# UNG_8088_EVB_LAN9252-SPI_LAN9252-1.net
KiCad netlist of a schematic drawn in Altium Designer
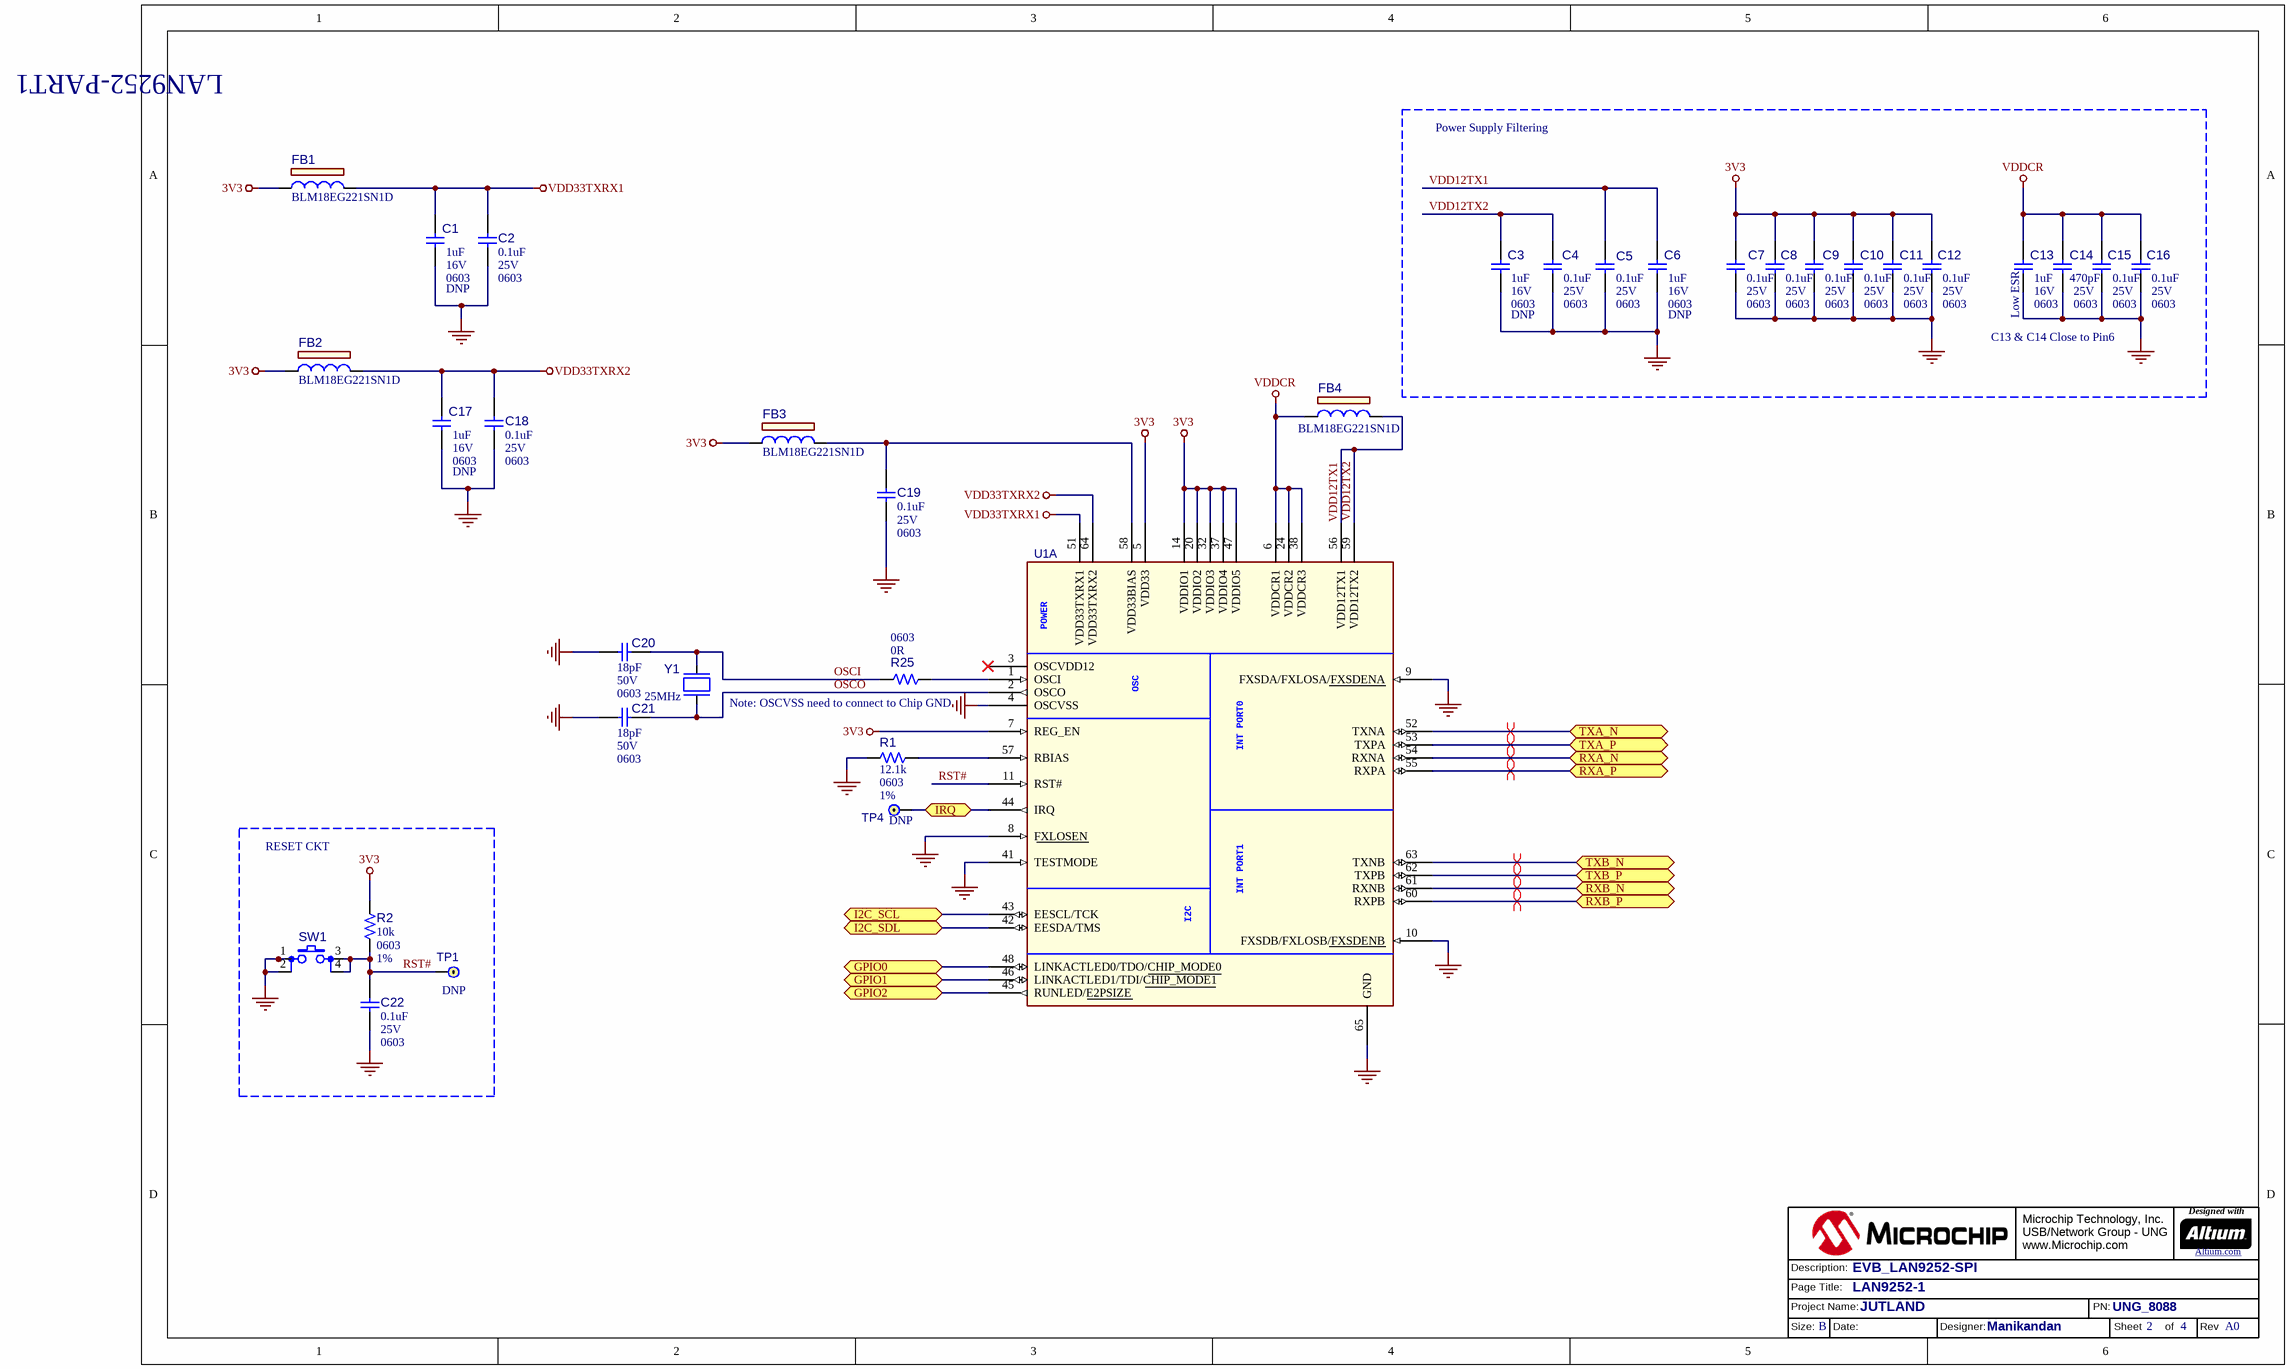
[diagram p0: UNG_8088_EVB_LAN9252-SPI_LAN9252-1.SchDoc]

(export (version "E")
  (design (tool "Eeschema 10.0.6"))
  (components
    (comp (ref "C1")
      (value "1uF")
      (footprint "CAP_C_0603")
      (description "Capacitor")
      (fields
        (field (name "VOLTAGE") "16V")
        (field (name "PACKAGE") "0603")
        (field (name "TOLERANCE") "10%")
        (field (name "POPULATED") "DNP")
        (field (name "Comment") "Capacitor NP")
      )
      (libsource (lib "MCHP-CDB-Offline") (part "Capacitor NP"))
    )
    (comp (ref "C2")
      (value "0.1uF")
      (footprint "CAP_C_0603")
      (description "Capacitor")
      (fields
        (field (name "VOLTAGE") "25V")
        (field (name "PACKAGE") "0603")
        (field (name "TOLERANCE") "20%")
        (field (name "Comment") "Capacitor NP")
      )
      (libsource (lib "MCHP-CDB-Offline") (part "Capacitor NP"))
    )
    (comp (ref "C3")
      (value "1uF")
      (footprint "CAP_C_0603")
      (description "Capacitor")
      (fields
        (field (name "VOLTAGE") "16V")
        (field (name "PACKAGE") "0603")
        (field (name "TOLERANCE") "10%")
        (field (name "POPULATED") "DNP")
        (field (name "Comment") "Capacitor NP")
      )
      (libsource (lib "MCHP-CDB-Offline") (part "Capacitor NP"))
    )
    (comp (ref "C4")
      (value "0.1uF")
      (footprint "CAP_C_0603")
      (description "Capacitor")
      (fields
        (field (name "VOLTAGE") "25V")
        (field (name "PACKAGE") "0603")
        (field (name "TOLERANCE") "20%")
        (field (name "Comment") "Capacitor NP")
      )
      (libsource (lib "MCHP-CDB-Offline") (part "Capacitor NP"))
    )
    (comp (ref "C5")
      (value "0.1uF")
      (footprint "CAP_C_0603")
      (description "Capacitor")
      (fields
        (field (name "VOLTAGE") "25V")
        (field (name "PACKAGE") "0603")
        (field (name "TOLERANCE") "20%")
        (field (name "Comment") "Capacitor NP")
      )
      (libsource (lib "MCHP-CDB-Offline") (part "Capacitor NP"))
    )
    (comp (ref "C6")
      (value "1uF")
      (footprint "CAP_C_0603")
      (description "Capacitor")
      (fields
        (field (name "VOLTAGE") "16V")
        (field (name "PACKAGE") "0603")
        (field (name "TOLERANCE") "10%")
        (field (name "POPULATED") "DNP")
        (field (name "Comment") "Capacitor NP")
      )
      (libsource (lib "MCHP-CDB-Offline") (part "Capacitor NP"))
    )
    (comp (ref "C7")
      (value "0.1uF")
      (footprint "CAP_C_0603")
      (description "Capacitor")
      (fields
        (field (name "VOLTAGE") "25V")
        (field (name "PACKAGE") "0603")
        (field (name "TOLERANCE") "20%")
        (field (name "Comment") "Capacitor NP")
      )
      (libsource (lib "MCHP-CDB-Offline") (part "Capacitor NP"))
    )
    (comp (ref "C8")
      (value "0.1uF")
      (footprint "CAP_C_0603")
      (description "Capacitor")
      (fields
        (field (name "VOLTAGE") "25V")
        (field (name "PACKAGE") "0603")
        (field (name "TOLERANCE") "20%")
        (field (name "Comment") "Capacitor NP")
      )
      (libsource (lib "MCHP-CDB-Offline") (part "Capacitor NP"))
    )
    (comp (ref "C9")
      (value "0.1uF")
      (footprint "CAP_C_0603")
      (description "Capacitor")
      (fields
        (field (name "VOLTAGE") "25V")
        (field (name "PACKAGE") "0603")
        (field (name "TOLERANCE") "20%")
        (field (name "Comment") "Capacitor NP")
      )
      (libsource (lib "MCHP-CDB-Offline") (part "Capacitor NP"))
    )
    (comp (ref "C10")
      (value "0.1uF")
      (footprint "CAP_C_0603")
      (description "Capacitor")
      (fields
        (field (name "VOLTAGE") "25V")
        (field (name "PACKAGE") "0603")
        (field (name "TOLERANCE") "20%")
        (field (name "Comment") "Capacitor NP")
      )
      (libsource (lib "MCHP-CDB-Offline") (part "Capacitor NP"))
    )
    (comp (ref "C11")
      (value "0.1uF")
      (footprint "CAP_C_0603")
      (description "Capacitor")
      (fields
        (field (name "VOLTAGE") "25V")
        (field (name "PACKAGE") "0603")
        (field (name "TOLERANCE") "20%")
        (field (name "Comment") "Capacitor NP")
      )
      (libsource (lib "MCHP-CDB-Offline") (part "Capacitor NP"))
    )
    (comp (ref "C12")
      (value "0.1uF")
      (footprint "CAP_C_0603")
      (description "Capacitor")
      (fields
        (field (name "VOLTAGE") "25V")
        (field (name "PACKAGE") "0603")
        (field (name "TOLERANCE") "20%")
        (field (name "Comment") "Capacitor NP")
      )
      (libsource (lib "MCHP-CDB-Offline") (part "Capacitor NP"))
    )
    (comp (ref "C13")
      (value "1uF")
      (footprint "CAP_C_0603")
      (description "Capacitor")
      (fields
        (field (name "VOLTAGE") "16V")
        (field (name "PACKAGE") "0603")
        (field (name "TOLERANCE") "10%")
        (field (name "Comment") "Capacitor NP")
      )
      (libsource (lib "MCHP-CDB-Offline") (part "Capacitor NP"))
    )
    (comp (ref "C14")
      (value "470pF")
      (footprint "CAP_C_0603")
      (description "Capacitor")
      (fields
        (field (name "VOLTAGE") "25V")
        (field (name "PACKAGE") "0603")
        (field (name "TOLERANCE") "5%")
        (field (name "Comment") "Capacitor NP")
      )
      (libsource (lib "MCHP-CDB-Offline") (part "Capacitor NP"))
    )
    (comp (ref "C15")
      (value "0.1uF")
      (footprint "CAP_C_0603")
      (description "Capacitor")
      (fields
        (field (name "VOLTAGE") "25V")
        (field (name "PACKAGE") "0603")
        (field (name "TOLERANCE") "20%")
        (field (name "Comment") "Capacitor NP")
      )
      (libsource (lib "MCHP-CDB-Offline") (part "Capacitor NP"))
    )
    (comp (ref "C16")
      (value "0.1uF")
      (footprint "CAP_C_0603")
      (description "Capacitor")
      (fields
        (field (name "VOLTAGE") "25V")
        (field (name "PACKAGE") "0603")
        (field (name "TOLERANCE") "20%")
        (field (name "Comment") "Capacitor NP")
      )
      (libsource (lib "MCHP-CDB-Offline") (part "Capacitor NP"))
    )
    (comp (ref "C17")
      (value "1uF")
      (footprint "CAP_C_0603")
      (description "Capacitor")
      (fields
        (field (name "VOLTAGE") "16V")
        (field (name "PACKAGE") "0603")
        (field (name "TOLERANCE") "10%")
        (field (name "POPULATED") "DNP")
        (field (name "Comment") "Capacitor NP")
      )
      (libsource (lib "MCHP-CDB-Offline") (part "Capacitor NP"))
    )
    (comp (ref "C18")
      (value "0.1uF")
      (footprint "CAP_C_0603")
      (description "Capacitor")
      (fields
        (field (name "VOLTAGE") "25V")
        (field (name "PACKAGE") "0603")
        (field (name "TOLERANCE") "20%")
        (field (name "Comment") "Capacitor NP")
      )
      (libsource (lib "MCHP-CDB-Offline") (part "Capacitor NP"))
    )
    (comp (ref "C19")
      (value "0.1uF")
      (footprint "CAP_C_0603")
      (description "Capacitor")
      (fields
        (field (name "VOLTAGE") "25V")
        (field (name "PACKAGE") "0603")
        (field (name "TOLERANCE") "20%")
        (field (name "Comment") "Capacitor NP")
      )
      (libsource (lib "MCHP-CDB-Offline") (part "Capacitor NP"))
    )
    (comp (ref "C20")
      (value "18pF")
      (footprint "CAP_C_0603")
      (description "Capacitor")
      (fields
        (field (name "VOLTAGE") "50V")
        (field (name "PACKAGE") "0603")
        (field (name "TOLERANCE") "5%")
        (field (name "Comment") "Capacitor NP")
      )
      (libsource (lib "MCHP-CDB-Offline") (part "Capacitor NP"))
    )
    (comp (ref "C21")
      (value "18pF")
      (footprint "CAP_C_0603")
      (description "Capacitor")
      (fields
        (field (name "VOLTAGE") "50V")
        (field (name "PACKAGE") "0603")
        (field (name "TOLERANCE") "5%")
        (field (name "Comment") "Capacitor NP")
      )
      (libsource (lib "MCHP-CDB-Offline") (part "Capacitor NP"))
    )
    (comp (ref "C22")
      (value "0.1uF")
      (footprint "CAP_C_0603")
      (description "Capacitor")
      (fields
        (field (name "VOLTAGE") "25V")
        (field (name "PACKAGE") "0603")
        (field (name "TOLERANCE") "20%")
        (field (name "Comment") "Capacitor NP")
      )
      (libsource (lib "MCHP-CDB-Offline") (part "Capacitor NP"))
    )
    (comp (ref "FB1")
      (value "BLM18EG221SN1D")
      (footprint "SMD_0603")
      (description "FERRITE BEAD 2A 220OHM 0603")
      (fields (field (name "Comment") "FERRITE BLM18EG221SN1D") (field (name "OWNER") "Manikandan"))
      (libsource (lib "UNG_MISC") (part "FERRITE BLM18EG221SN1D"))
    )
    (comp (ref "FB2")
      (value "BLM18EG221SN1D")
      (footprint "SMD_0603")
      (description "FERRITE BEAD 2A 220OHM 0603")
      (fields (field (name "Comment") "FERRITE BLM18EG221SN1D") (field (name "OWNER") "Manikandan"))
      (libsource (lib "UNG_MISC") (part "FERRITE BLM18EG221SN1D"))
    )
    (comp (ref "FB3")
      (value "BLM18EG221SN1D")
      (footprint "SMD_0603")
      (description "FERRITE BEAD 2A 220OHM 0603")
      (fields (field (name "Comment") "FERRITE BLM18EG221SN1D") (field (name "OWNER") "Manikandan"))
      (libsource (lib "UNG_MISC") (part "FERRITE BLM18EG221SN1D"))
    )
    (comp (ref "FB4")
      (value "BLM18EG221SN1D")
      (footprint "SMD_0603")
      (description "FERRITE BEAD 2A 220OHM 0603")
      (fields (field (name "Comment") "FERRITE BLM18EG221SN1D") (field (name "OWNER") "Manikandan"))
      (libsource (lib "UNG_MISC") (part "FERRITE BLM18EG221SN1D"))
    )
    (comp (ref "R1")
      (value "12.1k")
      (footprint "RES_C_0603")
      (description "Resistor")
      (fields
        (field (name "PACKAGE") "0603")
        (field (name "TOLERANCE") "1%")
        (field (name "VOLTAGE") "75V")
        (field (name "POWER") "1/10W")
      )
      (libsource (lib "MCHP-CDB-Offline") (part "Resistor"))
    )
    (comp (ref "R2")
      (value "10k")
      (footprint "RES_C_0603")
      (description "Resistor")
      (fields
        (field (name "PACKAGE") "0603")
        (field (name "TOLERANCE") "1%")
        (field (name "VOLTAGE") "100V")
        (field (name "POWER") "1/16W")
        (field (name "OWNER") "Jairuz Agang-ang")
      )
      (libsource (lib "MCHP-CDB-Offline") (part "Resistor"))
    )
    (comp (ref "R25")
      (value "0R")
      (footprint "RES_C_0603")
      (description "Resistor")
      (fields (field (name "PACKAGE") "0603") (field (name "POWER") "1/10W"))
      (libsource (lib "MCHP-CDB-Offline") (part "Resistor"))
    )
    (comp (ref "SW1")
      (value "Switch TACT 4 Pin PTS810")
      (footprint "SW_MOM_4M2X3M2")
      (description "SWITCH TACTILE SPST-NO 0.05A 16V PTS810 4.2 x 3.2 mm")
      (fields
        (field (name "MANUFACTURER") "C&K Components")
        (field (name "MANUFACTURER PART NUMBER") "PTS810 SJM 250 SMTR LFS")
      )
      (libsource (lib "UNG_SWITCHES") (part "Switch TACT 4 Pin PTS810"))
    )
    (comp (ref "TP1")
      (value "Jumper")
      (footprint "TP_PAD51D36")
      (description "Test Pad TH 51X36")
      (fields (field (name "MANUFACTURER PART NUMBER") "none") (field (name "POPULATED") "DNP"))
      (libsource (lib "UNG_CONNECTORS") (part "TEST PAD TH 51X36"))
    )
    (comp (ref "TP4")
      (value "Jumper")
      (footprint "TP_PAD51D36")
      (description "Test Pad TH 51X36")
      (fields (field (name "MANUFACTURER PART NUMBER") "none") (field (name "POPULATED") "DNP"))
      (libsource (lib "UNG_CONNECTORS") (part "TEST PAD TH 51X36"))
    )
    (comp (ref "U1")
      (value "~")
      (footprint "QFN-64_9x9_EP6SQ")
      (description "IC, 2/3-Port EtherCAT® Slave Controller, QFN64")
      (fields (field (name "OWNER") "Manikandan"))
      (libsource (lib "UNG_UNG") (part "LAN9252_QFN64"))
    )
    (comp (ref "Y1")
      (value "XTAL 25MHz HC49/US")
      (footprint "CRYSTAL_HC49-SMD-B")
      (description "Crystal 25MHz HC49/US")
      (fields
        (field (name "MANUFACTURER") "Murata Electronics North America")
        (field (name "FREQUENCY") "25MHz")
      )
      (libsource (lib "UNG_XTAL_OSC") (part "XTAL 25MHz HC49US"))
    )
  )
  (nets
    (net (code "1") (name "/GPIO0") (class "Default")
      (node (ref "U1") (pin "48") (pinfunction "LINKACTLED0/TDO/CHIP_MODE0_48") (pintype "bidirectional"))
    )
    (net (code "2") (name "/GPIO1") (class "Default")
      (node (ref "U1") (pin "46") (pinfunction "LINKACTLED1/TDI/CHIP_MODE1_46") (pintype "bidirectional"))
    )
    (net (code "3") (name "/GPIO2") (class "Default")
      (node (ref "U1") (pin "45") (pinfunction "RUNLED/E2PSIZE_45") (pintype "output"))
    )
    (net (code "4") (name "/I2C_SCL") (class "Default")
      (node (ref "U1") (pin "43") (pinfunction "EESCL/TCK_43") (pintype "bidirectional"))
    )
    (net (code "5") (name "/I2C_SDL") (class "Default")
      (node (ref "U1") (pin "42") (pinfunction "EESDA/TMS_42") (pintype "bidirectional"))
    )
    (net (code "6") (name "/IRQ") (class "Default")
      (node (ref "TP4") (pin "1") (pinfunction "P1_1") (pintype "passive"))
      (node (ref "U1") (pin "44") (pinfunction "IRQ_44") (pintype "output"))
    )
    (net (code "7") (name "/OSCI") (class "Default")
      (node (ref "C20") (pin "2") (pinfunction "2_2") (pintype "passive"))
      (node (ref "R25") (pin "1") (pinfunction "1_1") (pintype "passive"))
      (node (ref "Y1") (pin "2") (pinfunction "Osc2_2") (pintype "passive"))
    )
    (net (code "8") (name "/OSCO") (class "Default")
      (node (ref "C21") (pin "2") (pinfunction "2_2") (pintype "passive"))
      (node (ref "U1") (pin "2") (pinfunction "OSCO_2") (pintype "output"))
      (node (ref "Y1") (pin "1") (pinfunction "Osc1_1") (pintype "passive"))
    )
    (net (code "9") (name "/RST#") (class "Default")
      (node (ref "C22") (pin "2") (pinfunction "2_2") (pintype "passive"))
      (node (ref "R2") (pin "1") (pinfunction "1_1") (pintype "passive"))
      (node (ref "SW1") (pin "3") (pinfunction "3_3") (pintype "passive"))
      (node (ref "SW1") (pin "4") (pinfunction "4_4") (pintype "passive"))
      (node (ref "TP1") (pin "1") (pinfunction "P1_1") (pintype "passive"))
      (node (ref "U1") (pin "11") (pinfunction "RST#_11") (pintype "input"))
    )
    (net (code "10") (name "/RXA_N") (class "Default")
      (node (ref "U1") (pin "54") (pinfunction "RXNA_54") (pintype "bidirectional"))
    )
    (net (code "11") (name "/RXA_P") (class "Default")
      (node (ref "U1") (pin "55") (pinfunction "RXPA_55") (pintype "bidirectional"))
    )
    (net (code "12") (name "/RXB_N") (class "Default")
      (node (ref "U1") (pin "61") (pinfunction "RXNB_61") (pintype "bidirectional"))
    )
    (net (code "13") (name "/RXB_P") (class "Default")
      (node (ref "U1") (pin "60") (pinfunction "RXPB_60") (pintype "bidirectional"))
    )
    (net (code "14") (name "/TXA_N") (class "Default")
      (node (ref "U1") (pin "52") (pinfunction "TXNA_52") (pintype "bidirectional"))
    )
    (net (code "15") (name "/TXA_P") (class "Default")
      (node (ref "U1") (pin "53") (pinfunction "TXPA_53") (pintype "bidirectional"))
    )
    (net (code "16") (name "/TXB_N") (class "Default")
      (node (ref "U1") (pin "63") (pinfunction "TXNB_63") (pintype "bidirectional"))
    )
    (net (code "17") (name "/TXB_P") (class "Default")
      (node (ref "U1") (pin "62") (pinfunction "TXPB_62") (pintype "bidirectional"))
    )
    (net (code "18") (name "/VDD12TX1") (class "Default")
      (node (ref "C3") (pin "2") (pinfunction "2_2") (pintype "passive"))
      (node (ref "C4") (pin "2") (pinfunction "2_2") (pintype "passive"))
      (node (ref "C5") (pin "2") (pinfunction "2_2") (pintype "passive"))
      (node (ref "C6") (pin "2") (pinfunction "2_2") (pintype "passive"))
      (node (ref "FB4") (pin "2") (pinfunction "2_2") (pintype "passive"))
      (node (ref "U1") (pin "56") (pinfunction "VDD12TX1_56") (pintype "power_in"))
      (node (ref "U1") (pin "59") (pinfunction "VDD12TX2_59") (pintype "power_in"))
    )
    (net (code "19") (name "3V3") (class "Default")
      (node (ref "C10") (pin "2") (pinfunction "2_2") (pintype "passive"))
      (node (ref "C11") (pin "2") (pinfunction "2_2") (pintype "passive"))
      (node (ref "C12") (pin "2") (pinfunction "2_2") (pintype "passive"))
      (node (ref "C7") (pin "2") (pinfunction "2_2") (pintype "passive"))
      (node (ref "C8") (pin "2") (pinfunction "2_2") (pintype "passive"))
      (node (ref "C9") (pin "2") (pinfunction "2_2") (pintype "passive"))
      (node (ref "FB1") (pin "1") (pinfunction "1_1") (pintype "passive"))
      (node (ref "FB2") (pin "1") (pinfunction "1_1") (pintype "passive"))
      (node (ref "FB3") (pin "1") (pinfunction "1_1") (pintype "passive"))
      (node (ref "R2") (pin "2") (pinfunction "2_2") (pintype "passive"))
      (node (ref "U1") (pin "14") (pinfunction "VDDIO1_14") (pintype "power_in"))
      (node (ref "U1") (pin "20") (pinfunction "VDDIO2_20") (pintype "power_in"))
      (node (ref "U1") (pin "32") (pinfunction "VDDIO3_32") (pintype "power_in"))
      (node (ref "U1") (pin "37") (pinfunction "VDDIO4_37") (pintype "power_in"))
      (node (ref "U1") (pin "47") (pinfunction "VDDIO5_47") (pintype "power_in"))
      (node (ref "U1") (pin "5") (pinfunction "VDD33_5") (pintype "power_in"))
      (node (ref "U1") (pin "7") (pinfunction "REG_EN_7") (pintype "input"))
    )
    (net (code "20") (name "GND") (class "Default")
      (node (ref "C1") (pin "1") (pinfunction "1_1") (pintype "passive"))
      (node (ref "C10") (pin "1") (pinfunction "1_1") (pintype "passive"))
      (node (ref "C11") (pin "1") (pinfunction "1_1") (pintype "passive"))
      (node (ref "C12") (pin "1") (pinfunction "1_1") (pintype "passive"))
      (node (ref "C13") (pin "1") (pinfunction "1_1") (pintype "passive"))
      (node (ref "C14") (pin "1") (pinfunction "1_1") (pintype "passive"))
      (node (ref "C15") (pin "1") (pinfunction "1_1") (pintype "passive"))
      (node (ref "C16") (pin "1") (pinfunction "1_1") (pintype "passive"))
      (node (ref "C17") (pin "1") (pinfunction "1_1") (pintype "passive"))
      (node (ref "C18") (pin "1") (pinfunction "1_1") (pintype "passive"))
      (node (ref "C19") (pin "1") (pinfunction "1_1") (pintype "passive"))
      (node (ref "C2") (pin "1") (pinfunction "1_1") (pintype "passive"))
      (node (ref "C20") (pin "1") (pinfunction "1_1") (pintype "passive"))
      (node (ref "C21") (pin "1") (pinfunction "1_1") (pintype "passive"))
      (node (ref "C22") (pin "1") (pinfunction "1_1") (pintype "passive"))
      (node (ref "C3") (pin "1") (pinfunction "1_1") (pintype "passive"))
      (node (ref "C4") (pin "1") (pinfunction "1_1") (pintype "passive"))
      (node (ref "C5") (pin "1") (pinfunction "1_1") (pintype "passive"))
      (node (ref "C6") (pin "1") (pinfunction "1_1") (pintype "passive"))
      (node (ref "C7") (pin "1") (pinfunction "1_1") (pintype "passive"))
      (node (ref "C8") (pin "1") (pinfunction "1_1") (pintype "passive"))
      (node (ref "C9") (pin "1") (pinfunction "1_1") (pintype "passive"))
      (node (ref "R1") (pin "1") (pinfunction "1_1") (pintype "passive"))
      (node (ref "SW1") (pin "1") (pinfunction "1_1") (pintype "passive"))
      (node (ref "SW1") (pin "2") (pinfunction "2_2") (pintype "passive"))
      (node (ref "U1") (pin "10") (pinfunction "FXSDB/FXLOSB/FXSDENB_10") (pintype "input"))
      (node (ref "U1") (pin "4") (pinfunction "OSCVSS_4") (pintype "power_in"))
      (node (ref "U1") (pin "41") (pinfunction "TESTMODE_41") (pintype "input"))
      (node (ref "U1") (pin "65") (pinfunction "GND_65") (pintype "power_in"))
      (node (ref "U1") (pin "8") (pinfunction "FXLOSEN_8") (pintype "input"))
      (node (ref "U1") (pin "9") (pinfunction "FXSDA/FXLOSA/FXSDENA_9") (pintype "input"))
    )
    (net (code "21") (name "Net-(U1A-OSCI)") (class "Default")
      (node (ref "R25") (pin "2") (pinfunction "2_2") (pintype "passive"))
      (node (ref "U1") (pin "1") (pinfunction "OSCI_1") (pintype "input"))
    )
    (net (code "22") (name "Net-(U1A-RBIAS)") (class "Default")
      (node (ref "R1") (pin "2") (pinfunction "2_2") (pintype "passive"))
      (node (ref "U1") (pin "57") (pinfunction "RBIAS_57") (pintype "input"))
    )
    (net (code "23") (name "Net-(U1A-VDD33BIAS)") (class "Default")
      (node (ref "C19") (pin "2") (pinfunction "2_2") (pintype "passive"))
      (node (ref "FB3") (pin "2") (pinfunction "2_2") (pintype "passive"))
      (node (ref "U1") (pin "58") (pinfunction "VDD33BIAS_58") (pintype "power_in"))
    )
    (net (code "24") (name "VDD33TXRX1") (class "Default")
      (node (ref "C1") (pin "2") (pinfunction "2_2") (pintype "passive"))
      (node (ref "C2") (pin "2") (pinfunction "2_2") (pintype "passive"))
      (node (ref "FB1") (pin "2") (pinfunction "2_2") (pintype "passive"))
      (node (ref "U1") (pin "51") (pinfunction "VDD33TXRX1_51") (pintype "power_in"))
    )
    (net (code "25") (name "VDD33TXRX2") (class "Default")
      (node (ref "C17") (pin "2") (pinfunction "2_2") (pintype "passive"))
      (node (ref "C18") (pin "2") (pinfunction "2_2") (pintype "passive"))
      (node (ref "FB2") (pin "2") (pinfunction "2_2") (pintype "passive"))
      (node (ref "U1") (pin "64") (pinfunction "VDD33TXRX2_64") (pintype "power_in"))
    )
    (net (code "26") (name "VDDCR") (class "Default")
      (node (ref "C13") (pin "2") (pinfunction "2_2") (pintype "passive"))
      (node (ref "C14") (pin "2") (pinfunction "2_2") (pintype "passive"))
      (node (ref "C15") (pin "2") (pinfunction "2_2") (pintype "passive"))
      (node (ref "C16") (pin "2") (pinfunction "2_2") (pintype "passive"))
      (node (ref "FB4") (pin "1") (pinfunction "1_1") (pintype "passive"))
      (node (ref "U1") (pin "24") (pinfunction "VDDCR2_24") (pintype "power_in"))
      (node (ref "U1") (pin "38") (pinfunction "VDDCR3_38") (pintype "power_in"))
      (node (ref "U1") (pin "6") (pinfunction "VDDCR1_6") (pintype "power_in"))
    )
    (net (code "27") (name "unconnected-(U1A-OSCVDD12-Pad3)") (class "Default")
      (node (ref "U1") (pin "3") (pinfunction "OSCVDD12_3") (pintype "power_in+no_connect"))
    )
  )
)
